# Power_Distribution_-_Rear_turn_and_brake.net
KiCad netlist of a schematic drawn in Altium Designer
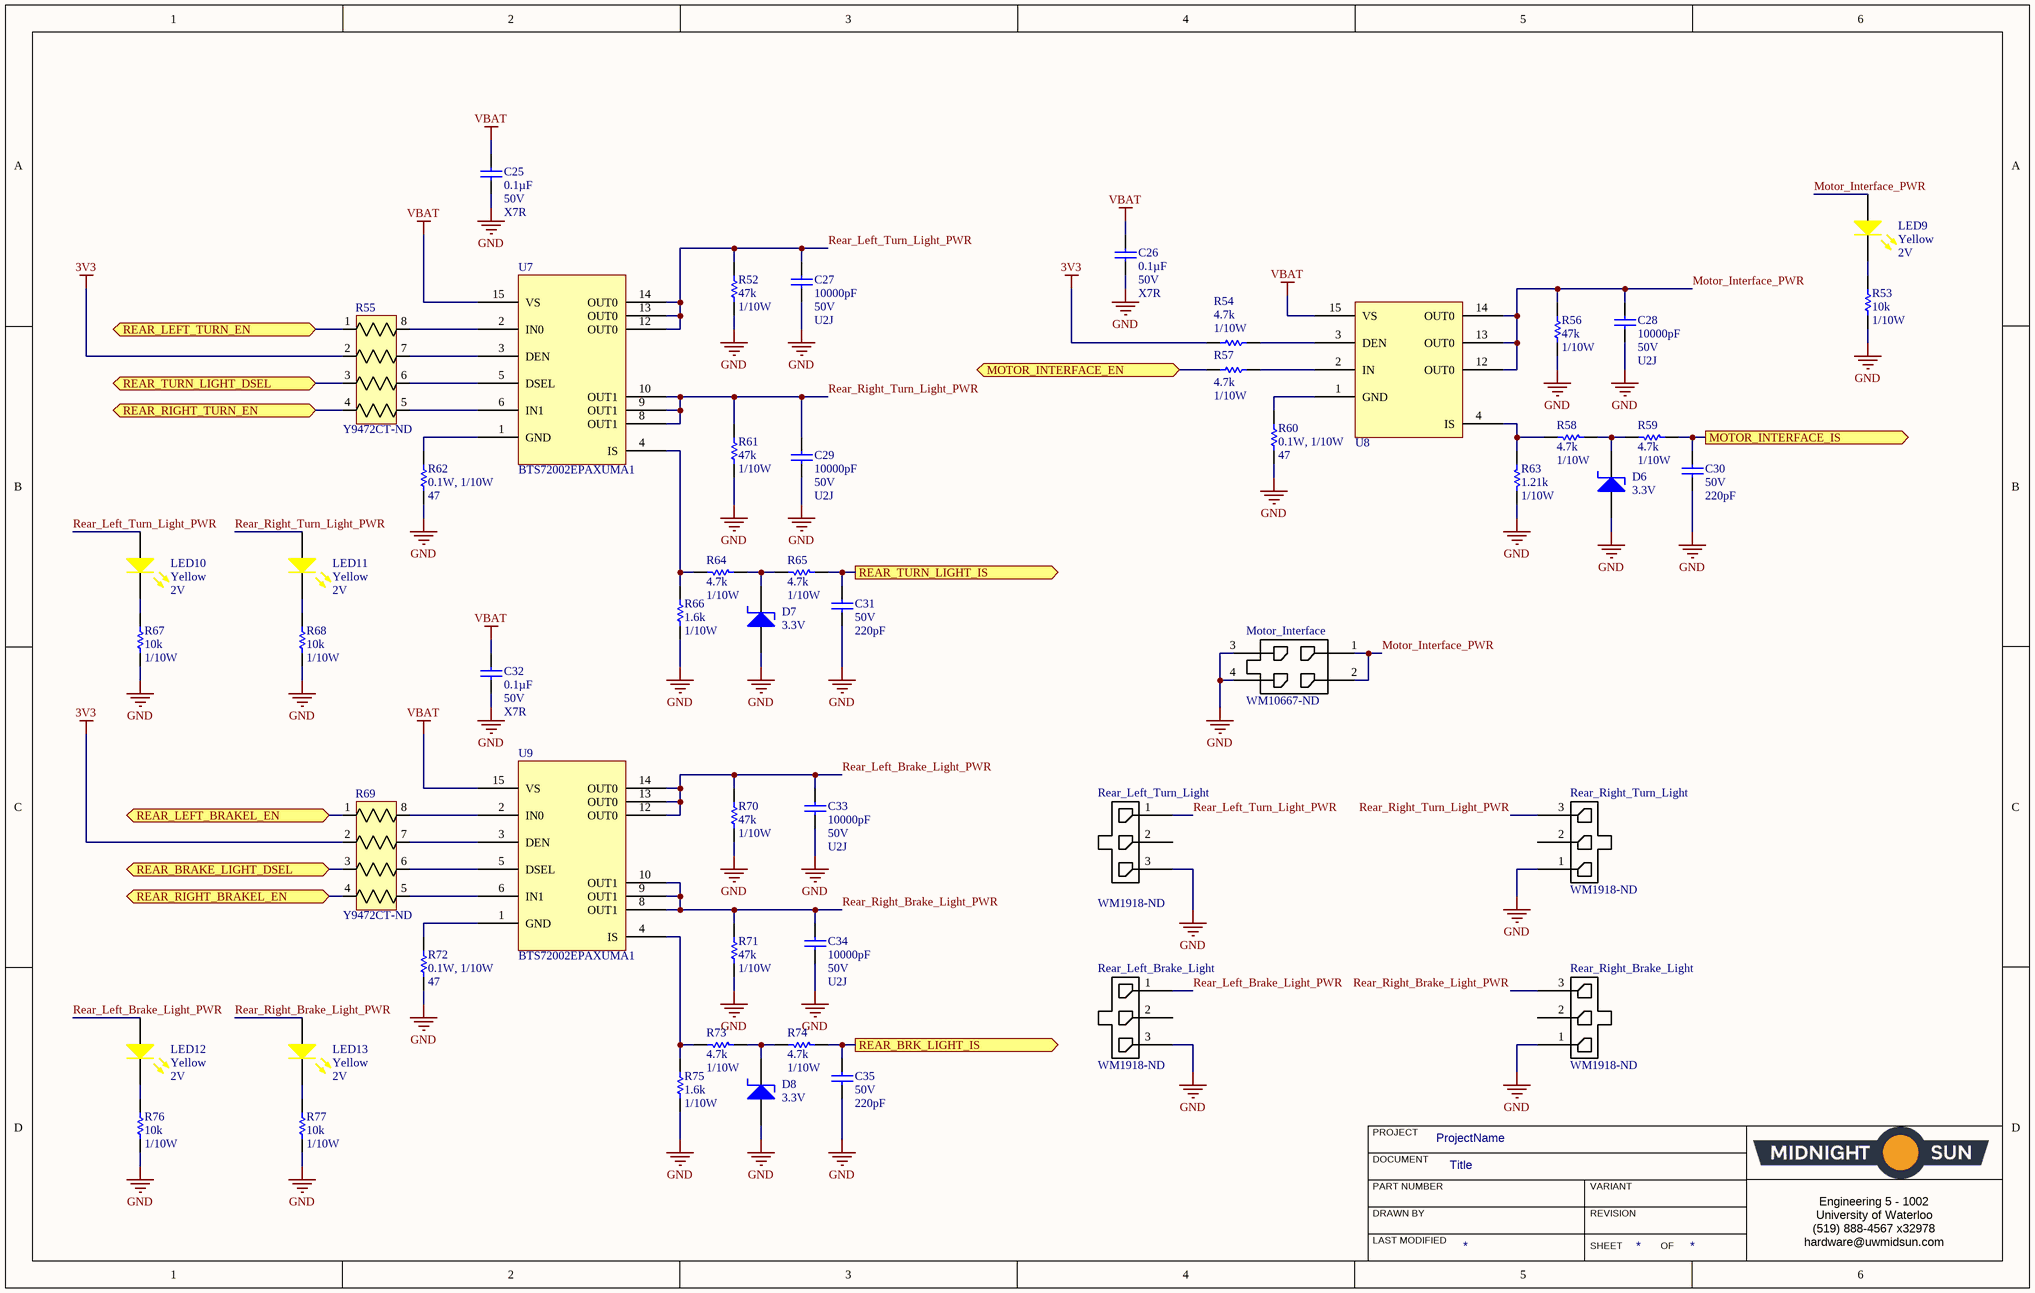
[diagram p0: Power Distribution - Rear turn and brake light, and Motor Interface.SchDoc]

(export (version "E")
  (design (tool "Eeschema 10.0.6"))
  (components
    (comp (ref "C25")
      (value "CAP CER 0.1UF 50V 10% X7R 0603")
      (footprint "CAP, 0603")
      (description "0.10µF ±10% 50V Ceramic Capacitor X7R 0603 (1608 Metric)")
      (fields
        (field (name "TOLERANCE") "±10%")
        (field (name "CAPACITANCE") "0.1µF")
        (field (name "VOLTAGE") "50V")
        (field (name "TEMPERATURE COEFFICIENT") "X7R")
      )
      (libsource (lib "Schematic Diagrams") (part "CAP CER 0.1UF 50V 10% X7R 0603"))
    )
    (comp (ref "C26")
      (value "CAP CER 0.1UF 50V 10% X7R 0603")
      (footprint "CAP, 0603")
      (description "0.10µF ±10% 50V Ceramic Capacitor X7R 0603 (1608 Metric)")
      (fields
        (field (name "TOLERANCE") "±10%")
        (field (name "CAPACITANCE") "0.1µF")
        (field (name "VOLTAGE") "50V")
        (field (name "TEMPERATURE COEFFICIENT") "X7R")
      )
      (libsource (lib "Schematic Diagrams") (part "CAP CER 0.1UF 50V 10% X7R 0603"))
    )
    (comp (ref "C27")
      (value "CAP CER 10nF 50V 5% X7R 0603")
      (footprint "CAP, 0603")
      (description "10000pF ±5% 50V Ceramic Capacitor U2J 0603 (1608 Metric)")
      (fields
        (field (name "TOLERANCE") "±5%")
        (field (name "CAPACITANCE") "10000pF")
        (field (name "VOLTAGE") "50V")
        (field (name "TEMPERATURE COEFFICIENT") "U2J")
      )
      (libsource (lib "Schematic Diagrams") (part "CAP CER 10nF 50V 5% X7R 0603"))
    )
    (comp (ref "C28")
      (value "CAP CER 10nF 50V 5% X7R 0603")
      (footprint "CAP, 0603")
      (description "10000pF ±5% 50V Ceramic Capacitor U2J 0603 (1608 Metric)")
      (fields
        (field (name "TOLERANCE") "±5%")
        (field (name "CAPACITANCE") "10000pF")
        (field (name "VOLTAGE") "50V")
        (field (name "TEMPERATURE COEFFICIENT") "U2J")
      )
      (libsource (lib "Schematic Diagrams") (part "CAP CER 10nF 50V 5% X7R 0603"))
    )
    (comp (ref "C29")
      (value "CAP CER 10nF 50V 5% X7R 0603")
      (footprint "CAP, 0603")
      (description "10000pF ±5% 50V Ceramic Capacitor U2J 0603 (1608 Metric)")
      (fields
        (field (name "TOLERANCE") "±5%")
        (field (name "CAPACITANCE") "10000pF")
        (field (name "VOLTAGE") "50V")
        (field (name "TEMPERATURE COEFFICIENT") "U2J")
      )
      (libsource (lib "Schematic Diagrams") (part "CAP CER 10nF 50V 5% X7R 0603"))
    )
    (comp (ref "C30")
      (value "CAP CER 220PF 50V C0G/NP0 0603")
      (footprint "CAP, 0603")
      (description "220pF ±5% 50V Ceramic Capacitor C0G, NP0 0603 (1608 Metric)")
      (fields
        (field (name "MANUFACTURER") "KEMET")
        (field (name "TOLERANCE") "5%")
        (field (name "VOLTAGE RATING") "50V")
        (field (name "CAPACITANCE") "220pF")
      )
      (libsource (lib "Schematic Diagrams") (part "CAP CER 220PF 50V C0G/NP0 0603"))
    )
    (comp (ref "C31")
      (value "CAP CER 220PF 50V C0G/NP0 0603")
      (footprint "CAP, 0603")
      (description "220pF ±5% 50V Ceramic Capacitor C0G, NP0 0603 (1608 Metric)")
      (fields
        (field (name "MANUFACTURER") "KEMET")
        (field (name "TOLERANCE") "5%")
        (field (name "VOLTAGE RATING") "50V")
        (field (name "CAPACITANCE") "220pF")
      )
      (libsource (lib "Schematic Diagrams") (part "CAP CER 220PF 50V C0G/NP0 0603"))
    )
    (comp (ref "C32")
      (value "CAP CER 0.1UF 50V 10% X7R 0603")
      (footprint "CAP, 0603")
      (description "0.10µF ±10% 50V Ceramic Capacitor X7R 0603 (1608 Metric)")
      (fields
        (field (name "TOLERANCE") "±10%")
        (field (name "CAPACITANCE") "0.1µF")
        (field (name "VOLTAGE") "50V")
        (field (name "TEMPERATURE COEFFICIENT") "X7R")
      )
      (libsource (lib "Schematic Diagrams") (part "CAP CER 0.1UF 50V 10% X7R 0603"))
    )
    (comp (ref "C33")
      (value "CAP CER 10nF 50V 5% X7R 0603")
      (footprint "CAP, 0603")
      (description "10000pF ±5% 50V Ceramic Capacitor U2J 0603 (1608 Metric)")
      (fields
        (field (name "TOLERANCE") "±5%")
        (field (name "CAPACITANCE") "10000pF")
        (field (name "VOLTAGE") "50V")
        (field (name "TEMPERATURE COEFFICIENT") "U2J")
      )
      (libsource (lib "Schematic Diagrams") (part "CAP CER 10nF 50V 5% X7R 0603"))
    )
    (comp (ref "C34")
      (value "CAP CER 10nF 50V 5% X7R 0603")
      (footprint "CAP, 0603")
      (description "10000pF ±5% 50V Ceramic Capacitor U2J 0603 (1608 Metric)")
      (fields
        (field (name "TOLERANCE") "±5%")
        (field (name "CAPACITANCE") "10000pF")
        (field (name "VOLTAGE") "50V")
        (field (name "TEMPERATURE COEFFICIENT") "U2J")
      )
      (libsource (lib "Schematic Diagrams") (part "CAP CER 10nF 50V 5% X7R 0603"))
    )
    (comp (ref "C35")
      (value "CAP CER 220PF 50V C0G/NP0 0603")
      (footprint "CAP, 0603")
      (description "220pF ±5% 50V Ceramic Capacitor C0G, NP0 0603 (1608 Metric)")
      (fields
        (field (name "MANUFACTURER") "KEMET")
        (field (name "TOLERANCE") "5%")
        (field (name "VOLTAGE RATING") "50V")
        (field (name "CAPACITANCE") "220pF")
      )
      (libsource (lib "Schematic Diagrams") (part "CAP CER 220PF 50V C0G/NP0 0603"))
    )
    (comp (ref "D6")
      (value "DIODE ZENER 3.3V 200MW SOD323")
      (footprint "sod-323")
      (description "Zener Diode 3.3V 200mW ±5% Surface Mount SOD-323")
      (fields (field (name "VOLTAGE") "3.3V"))
      (libsource (lib "Schematic Diagrams") (part "DIODE ZENER 3.3V 200MW SOD323"))
    )
    (comp (ref "D7")
      (value "DIODE ZENER 3.3V 200MW SOD323")
      (footprint "sod-323")
      (description "Zener Diode 3.3V 200mW ±5% Surface Mount SOD-323")
      (fields (field (name "VOLTAGE") "3.3V"))
      (libsource (lib "Schematic Diagrams") (part "DIODE ZENER 3.3V 200MW SOD323"))
    )
    (comp (ref "D8")
      (value "DIODE ZENER 3.3V 200MW SOD323")
      (footprint "sod-323")
      (description "Zener Diode 3.3V 200mW ±5% Surface Mount SOD-323")
      (fields (field (name "VOLTAGE") "3.3V"))
      (libsource (lib "Schematic Diagrams") (part "DIODE ZENER 3.3V 200MW SOD323"))
    )
    (comp (ref "LED9")
      (value "LED YELLOW CLEAR 2.1V 0603")
      (footprint "LED_0603")
      (description "Yellow 590nm LED Indication - Discrete 2V 0603 (1608 Metric)")
      (fields
        (field (name "MANUFACTURER") "Wurth Electronics Inc.")
        (field (name "MANUFACTURER PART NUMBER") "150060YS75000")
        (field (name "COLOR") "Yellow")
        (field (name "VOLTAGE - FORWARD (VF) (TYP)") "2V")
      )
      (libsource (lib "Schematic Diagrams") (part "LED YELLOW CLEAR 2.1V 0603"))
    )
    (comp (ref "LED10")
      (value "LED YELLOW CLEAR 2.1V 0603")
      (footprint "LED_0603")
      (description "Yellow 590nm LED Indication - Discrete 2V 0603 (1608 Metric)")
      (fields
        (field (name "MANUFACTURER") "Wurth Electronics Inc.")
        (field (name "MANUFACTURER PART NUMBER") "150060YS75000")
        (field (name "COLOR") "Yellow")
        (field (name "VOLTAGE - FORWARD (VF) (TYP)") "2V")
      )
      (libsource (lib "Schematic Diagrams") (part "LED YELLOW CLEAR 2.1V 0603"))
    )
    (comp (ref "LED11")
      (value "LED YELLOW CLEAR 2.1V 0603")
      (footprint "LED_0603")
      (description "Yellow 590nm LED Indication - Discrete 2V 0603 (1608 Metric)")
      (fields
        (field (name "MANUFACTURER") "Wurth Electronics Inc.")
        (field (name "MANUFACTURER PART NUMBER") "150060YS75000")
        (field (name "COLOR") "Yellow")
        (field (name "VOLTAGE - FORWARD (VF) (TYP)") "2V")
      )
      (libsource (lib "Schematic Diagrams") (part "LED YELLOW CLEAR 2.1V 0603"))
    )
    (comp (ref "LED12")
      (value "LED YELLOW CLEAR 2.1V 0603")
      (footprint "LED_0603")
      (description "Yellow 590nm LED Indication - Discrete 2V 0603 (1608 Metric)")
      (fields
        (field (name "MANUFACTURER") "Wurth Electronics Inc.")
        (field (name "MANUFACTURER PART NUMBER") "150060YS75000")
        (field (name "COLOR") "Yellow")
        (field (name "VOLTAGE - FORWARD (VF) (TYP)") "2V")
      )
      (libsource (lib "Schematic Diagrams") (part "LED YELLOW CLEAR 2.1V 0603"))
    )
    (comp (ref "LED13")
      (value "LED YELLOW CLEAR 2.1V 0603")
      (footprint "LED_0603")
      (description "Yellow 590nm LED Indication - Discrete 2V 0603 (1608 Metric)")
      (fields
        (field (name "MANUFACTURER") "Wurth Electronics Inc.")
        (field (name "MANUFACTURER PART NUMBER") "150060YS75000")
        (field (name "COLOR") "Yellow")
        (field (name "VOLTAGE - FORWARD (VF) (TYP)") "2V")
      )
      (libsource (lib "Schematic Diagrams") (part "LED YELLOW CLEAR 2.1V 0603"))
    )
    (comp (ref "Motor_Interface")
      (value "CONN 4POS MICRO-FIT 3mm")
      (footprint "CONN 4POS MICROFIT (2x2)")
      (fields
        (field (name "MANUFACTURER") "Molex, LLC")
        (field (name "MANUFACTURER PART NUMBER") "430450427")
        (field (name "SUPPLIER PART NUMBER 1") "WM10667-ND")
      )
      (libsource (lib "Schematic Diagrams") (part "CONN 4POS MICRO-FIT 3mm"))
    )
    (comp (ref "R52")
      (value "RES 47K OHM 1% 1/10W 0603")
      (footprint "RES, 0603")
      (description "47 kOhms ±1% 0.1W, 1/10W Chip Resistor 0603 (1608 Metric) Automotive AEC-Q200 Thick Film")
      (fields
        (field (name "MANUFACTURER") "Panasonic")
        (field (name "MANUFACTURER PART NUMBER") "ERJ3EKF4702V")
        (field (name "RESISTANCE") "47k")
        (field (name "POWER RATING") "1/10W")
      )
      (libsource (lib "Schematic Diagrams") (part "RES 47K OHM 1% 1/10W 0603"))
    )
    (comp (ref "R53")
      (value "RES 10K OHM 1% 1/10W 0603")
      (footprint "RES, 0603")
      (description "RES SMD 10K OHM 1% 1/10W 0603")
      (fields
        (field (name "TOLERANCE") "±1%")
        (field (name "RESISTANCE") "10k")
        (field (name "POWER") "1/10W")
      )
      (libsource (lib "Schematic Diagrams") (part "RES 10K OHM 1% 1/10W 0603"))
    )
    (comp (ref "R54")
      (value "RES 4.7K OHM 1% 1/10W 0603")
      (footprint "RES, 0603")
      (description "4.7k Ohm ±1% 0.1W, 1/10W Chip Resistor 0603 (1608 Metric) Moisture Resistant Thick Film")
      (fields
        (field (name "TOLERANCE") "±1%")
        (field (name "RESISTANCE (OHMS)") "4.7k")
        (field (name "POWER (WATTS)") "1/10W")
      )
      (libsource (lib "Schematic Diagrams") (part "RES 4.7K OHM 1% 1/10W 0603"))
    )
    (comp (ref "R55")
      (value "RES ARRAY 4 RES 4.7K OHM 1206")
      (footprint "RES ARRAY 4RES 1206")
      (fields (field (name "TOLERANCE") "±5%") (field (name "SUPPLIER PART NUMBER 1") "Y9472CT-ND"))
      (libsource (lib "Schematic Diagrams") (part "RES ARRAY 4 RES 4.7K OHM 1206"))
    )
    (comp (ref "R56")
      (value "RES 47K OHM 1% 1/10W 0603")
      (footprint "RES, 0603")
      (description "47 kOhms ±1% 0.1W, 1/10W Chip Resistor 0603 (1608 Metric) Automotive AEC-Q200 Thick Film")
      (fields
        (field (name "MANUFACTURER") "Panasonic")
        (field (name "MANUFACTURER PART NUMBER") "ERJ3EKF4702V")
        (field (name "RESISTANCE") "47k")
        (field (name "POWER RATING") "1/10W")
      )
      (libsource (lib "Schematic Diagrams") (part "RES 47K OHM 1% 1/10W 0603"))
    )
    (comp (ref "R57")
      (value "RES 4.7K OHM 1% 1/10W 0603")
      (footprint "RES, 0603")
      (description "4.7k Ohm ±1% 0.1W, 1/10W Chip Resistor 0603 (1608 Metric) Moisture Resistant Thick Film")
      (fields
        (field (name "TOLERANCE") "±1%")
        (field (name "RESISTANCE (OHMS)") "4.7k")
        (field (name "POWER (WATTS)") "1/10W")
      )
      (libsource (lib "Schematic Diagrams") (part "RES 4.7K OHM 1% 1/10W 0603"))
    )
    (comp (ref "R58")
      (value "RES 4.7K OHM 1% 1/10W 0603")
      (footprint "RES, 0603")
      (description "4.7k Ohm ±1% 0.1W, 1/10W Chip Resistor 0603 (1608 Metric) Moisture Resistant Thick Film")
      (fields
        (field (name "TOLERANCE") "±1%")
        (field (name "RESISTANCE (OHMS)") "4.7k")
        (field (name "POWER (WATTS)") "1/10W")
      )
      (libsource (lib "Schematic Diagrams") (part "RES 4.7K OHM 1% 1/10W 0603"))
    )
    (comp (ref "R59")
      (value "RES 4.7K OHM 1% 1/10W 0603")
      (footprint "RES, 0603")
      (description "4.7k Ohm ±1% 0.1W, 1/10W Chip Resistor 0603 (1608 Metric) Moisture Resistant Thick Film")
      (fields
        (field (name "TOLERANCE") "±1%")
        (field (name "RESISTANCE (OHMS)") "4.7k")
        (field (name "POWER (WATTS)") "1/10W")
      )
      (libsource (lib "Schematic Diagrams") (part "RES 4.7K OHM 1% 1/10W 0603"))
    )
    (comp (ref "R60")
      (value "RES SMD 47 OHM 1% 1/10W 0603")
      (footprint "RES, 0603")
      (fields
        (field (name "TOLERANCE") "±1%")
        (field (name "POWER (WATTS)") "0.1W, 1/10W")
        (field (name "VALUES") "47")
      )
      (libsource (lib "Schematic Diagrams") (part "RES SMD 47 OHM 1% 1/10W 0603"))
    )
    (comp (ref "R61")
      (value "RES 47K OHM 1% 1/10W 0603")
      (footprint "RES, 0603")
      (description "47 kOhms ±1% 0.1W, 1/10W Chip Resistor 0603 (1608 Metric) Automotive AEC-Q200 Thick Film")
      (fields
        (field (name "MANUFACTURER") "Panasonic")
        (field (name "MANUFACTURER PART NUMBER") "ERJ3EKF4702V")
        (field (name "RESISTANCE") "47k")
        (field (name "POWER RATING") "1/10W")
      )
      (libsource (lib "Schematic Diagrams") (part "RES 47K OHM 1% 1/10W 0603"))
    )
    (comp (ref "R62")
      (value "RES SMD 47 OHM 1% 1/10W 0603")
      (footprint "RES, 0603")
      (fields
        (field (name "TOLERANCE") "±1%")
        (field (name "POWER (WATTS)") "0.1W, 1/10W")
        (field (name "VALUES") "47")
      )
      (libsource (lib "Schematic Diagrams") (part "RES SMD 47 OHM 1% 1/10W 0603"))
    )
    (comp (ref "R63")
      (value "RES 1.21K OHM 1% 1/10W 0603")
      (footprint "RES, 0603")
      (description "1.21k Ohm ±1% 0.1W, 1/10W Chip Resistor 0603 (1608 Metric) Moisture Resistant Thick Film")
      (fields
        (field (name "TOLERANCE") "±1%")
        (field (name "RESISTANCE") "1.21k")
        (field (name "POWER") "1/10W")
      )
      (libsource (lib "Schematic Diagrams") (part "RES 1.21K OHM 1% 1/10W 0603"))
    )
    (comp (ref "R64")
      (value "RES 4.7K OHM 1% 1/10W 0603")
      (footprint "RES, 0603")
      (description "4.7k Ohm ±1% 0.1W, 1/10W Chip Resistor 0603 (1608 Metric) Moisture Resistant Thick Film")
      (fields
        (field (name "TOLERANCE") "±1%")
        (field (name "RESISTANCE (OHMS)") "4.7k")
        (field (name "POWER (WATTS)") "1/10W")
      )
      (libsource (lib "Schematic Diagrams") (part "RES 4.7K OHM 1% 1/10W 0603"))
    )
    (comp (ref "R65")
      (value "RES 4.7K OHM 1% 1/10W 0603")
      (footprint "RES, 0603")
      (description "4.7k Ohm ±1% 0.1W, 1/10W Chip Resistor 0603 (1608 Metric) Moisture Resistant Thick Film")
      (fields
        (field (name "TOLERANCE") "±1%")
        (field (name "RESISTANCE (OHMS)") "4.7k")
        (field (name "POWER (WATTS)") "1/10W")
      )
      (libsource (lib "Schematic Diagrams") (part "RES 4.7K OHM 1% 1/10W 0603"))
    )
    (comp (ref "R66")
      (value "RES 1.6K OHM 1% 1/10W 0603")
      (footprint "RES, 0603")
      (description "1.6 kOhms ±1% 0.1W, 1/10W Chip Resistor 0603 (1608 Metric) Moisture Resistant Thick Film")
      (fields
        (field (name "MANUFACTURER") "Yageo")
        (field (name "MANUFACTURER PART NUMBER") "RC0603FR-071K6L")
        (field (name "RESISTANCE") "1.6k")
        (field (name "POWER RATING") "1/10W")
      )
      (libsource (lib "Schematic Diagrams") (part "RES 1.6K OHM 1% 1/10W 0603"))
    )
    (comp (ref "R67")
      (value "RES 10K OHM 1% 1/10W 0603")
      (footprint "RES, 0603")
      (description "RES SMD 10K OHM 1% 1/10W 0603")
      (fields
        (field (name "TOLERANCE") "±1%")
        (field (name "RESISTANCE") "10k")
        (field (name "POWER") "1/10W")
      )
      (libsource (lib "Schematic Diagrams") (part "RES 10K OHM 1% 1/10W 0603"))
    )
    (comp (ref "R68")
      (value "RES 10K OHM 1% 1/10W 0603")
      (footprint "RES, 0603")
      (description "RES SMD 10K OHM 1% 1/10W 0603")
      (fields
        (field (name "TOLERANCE") "±1%")
        (field (name "RESISTANCE") "10k")
        (field (name "POWER") "1/10W")
      )
      (libsource (lib "Schematic Diagrams") (part "RES 10K OHM 1% 1/10W 0603"))
    )
    (comp (ref "R69")
      (value "RES ARRAY 4 RES 4.7K OHM 1206")
      (footprint "RES ARRAY 4RES 1206")
      (fields (field (name "TOLERANCE") "±5%") (field (name "SUPPLIER PART NUMBER 1") "Y9472CT-ND"))
      (libsource (lib "Schematic Diagrams") (part "RES ARRAY 4 RES 4.7K OHM 1206"))
    )
    (comp (ref "R70")
      (value "RES 47K OHM 1% 1/10W 0603")
      (footprint "RES, 0603")
      (description "47 kOhms ±1% 0.1W, 1/10W Chip Resistor 0603 (1608 Metric) Automotive AEC-Q200 Thick Film")
      (fields
        (field (name "MANUFACTURER") "Panasonic")
        (field (name "MANUFACTURER PART NUMBER") "ERJ3EKF4702V")
        (field (name "RESISTANCE") "47k")
        (field (name "POWER RATING") "1/10W")
      )
      (libsource (lib "Schematic Diagrams") (part "RES 47K OHM 1% 1/10W 0603"))
    )
    (comp (ref "R71")
      (value "RES 47K OHM 1% 1/10W 0603")
      (footprint "RES, 0603")
      (description "47 kOhms ±1% 0.1W, 1/10W Chip Resistor 0603 (1608 Metric) Automotive AEC-Q200 Thick Film")
      (fields
        (field (name "MANUFACTURER") "Panasonic")
        (field (name "MANUFACTURER PART NUMBER") "ERJ3EKF4702V")
        (field (name "RESISTANCE") "47k")
        (field (name "POWER RATING") "1/10W")
      )
      (libsource (lib "Schematic Diagrams") (part "RES 47K OHM 1% 1/10W 0603"))
    )
    (comp (ref "R72")
      (value "RES SMD 47 OHM 1% 1/10W 0603")
      (footprint "RES, 0603")
      (fields
        (field (name "TOLERANCE") "±1%")
        (field (name "POWER (WATTS)") "0.1W, 1/10W")
        (field (name "VALUES") "47")
      )
      (libsource (lib "Schematic Diagrams") (part "RES SMD 47 OHM 1% 1/10W 0603"))
    )
    (comp (ref "R73")
      (value "RES 4.7K OHM 1% 1/10W 0603")
      (footprint "RES, 0603")
      (description "4.7k Ohm ±1% 0.1W, 1/10W Chip Resistor 0603 (1608 Metric) Moisture Resistant Thick Film")
      (fields
        (field (name "TOLERANCE") "±1%")
        (field (name "RESISTANCE (OHMS)") "4.7k")
        (field (name "POWER (WATTS)") "1/10W")
      )
      (libsource (lib "Schematic Diagrams") (part "RES 4.7K OHM 1% 1/10W 0603"))
    )
    (comp (ref "R74")
      (value "RES 4.7K OHM 1% 1/10W 0603")
      (footprint "RES, 0603")
      (description "4.7k Ohm ±1% 0.1W, 1/10W Chip Resistor 0603 (1608 Metric) Moisture Resistant Thick Film")
      (fields
        (field (name "TOLERANCE") "±1%")
        (field (name "RESISTANCE (OHMS)") "4.7k")
        (field (name "POWER (WATTS)") "1/10W")
      )
      (libsource (lib "Schematic Diagrams") (part "RES 4.7K OHM 1% 1/10W 0603"))
    )
    (comp (ref "R75")
      (value "RES 1.6K OHM 1% 1/10W 0603")
      (footprint "RES, 0603")
      (description "1.6 kOhms ±1% 0.1W, 1/10W Chip Resistor 0603 (1608 Metric) Moisture Resistant Thick Film")
      (fields
        (field (name "MANUFACTURER") "Yageo")
        (field (name "MANUFACTURER PART NUMBER") "RC0603FR-071K6L")
        (field (name "RESISTANCE") "1.6k")
        (field (name "POWER RATING") "1/10W")
      )
      (libsource (lib "Schematic Diagrams") (part "RES 1.6K OHM 1% 1/10W 0603"))
    )
    (comp (ref "R76")
      (value "RES 10K OHM 1% 1/10W 0603")
      (footprint "RES, 0603")
      (description "RES SMD 10K OHM 1% 1/10W 0603")
      (fields
        (field (name "TOLERANCE") "±1%")
        (field (name "RESISTANCE") "10k")
        (field (name "POWER") "1/10W")
      )
      (libsource (lib "Schematic Diagrams") (part "RES 10K OHM 1% 1/10W 0603"))
    )
    (comp (ref "R77")
      (value "RES 10K OHM 1% 1/10W 0603")
      (footprint "RES, 0603")
      (description "RES SMD 10K OHM 1% 1/10W 0603")
      (fields
        (field (name "TOLERANCE") "±1%")
        (field (name "RESISTANCE") "10k")
        (field (name "POWER") "1/10W")
      )
      (libsource (lib "Schematic Diagrams") (part "RES 10K OHM 1% 1/10W 0603"))
    )
    (comp (ref "Rear_Left_Brake_Light")
      (value "CONN 3POS MICROFIT")
      (footprint "CONN, 3 POS MICROFIT")
      (description "Connector Header Through Hole 3 position 0.118\" (3.00mm)")
      (fields (field (name "SUPPLIER PART NUMBER 1") "WM1918-ND"))
      (libsource (lib "Schematic Diagrams") (part "CONN 3POS MICROFIT"))
    )
    (comp (ref "Rear_Left_Turn_Light")
      (value "CONN 3POS MICROFIT")
      (footprint "CONN, 3 POS MICROFIT")
      (description "Connector Header Through Hole 3 position 0.118\" (3.00mm)")
      (fields (field (name "SUPPLIER PART NUMBER 1") "WM1918-ND"))
      (libsource (lib "Schematic Diagrams") (part "CONN 3POS MICROFIT"))
    )
    (comp (ref "Rear_Right_Brake_Light")
      (value "CONN 3POS MICROFIT")
      (footprint "CONN, 3 POS MICROFIT")
      (description "Connector Header Through Hole 3 position 0.118\" (3.00mm)")
      (fields (field (name "SUPPLIER PART NUMBER 1") "WM1918-ND"))
      (libsource (lib "Schematic Diagrams") (part "CONN 3POS MICROFIT"))
    )
    (comp (ref "Rear_Right_Turn_Light")
      (value "CONN 3POS MICROFIT")
      (footprint "CONN, 3 POS MICROFIT")
      (description "Connector Header Through Hole 3 position 0.118\" (3.00mm)")
      (fields (field (name "SUPPLIER PART NUMBER 1") "WM1918-ND"))
      (libsource (lib "Schematic Diagrams") (part "CONN 3POS MICROFIT"))
    )
    (comp (ref "U7")
      (value "IC LOAD SWITCH BTS7200-2EPA PG-TSDSO-14_1")
      (footprint "IC LOAD SWITCH PG-TSDSO-14-22")
      (description "Power Switch/Driver 1:1 N-Channel 1.2A PG-TSDSO-14-22")
      (fields
        (field (name "MANUFACTURER") "Infineon")
        (field (name "MANUFACTURER PART NUMBER") "BTS72002EPAXUMA1")
      )
      (libsource (lib "Schematic Diagrams") (part "IC LOAD SWITCH BTS7200-2EPA PG-TSDSO-14_1"))
    )
    (comp (ref "U8")
      (value "IC LOAD SWITCH BTS70401EPA PG-TSDSO-14-22")
      (footprint "IC LOAD SWITCH PG-TSDSO-14-22")
      (description "Power Switch/Driver 1:1 N-Channel 4.5A PG-TSDSO-14-22")
      (fields
        (field (name "MANUFACTURER") "Infineon")
        (field (name "MANUFACTURER PART NUMBER") "BTS70401EPAXUMA1")
      )
      (libsource (lib "Schematic Diagrams") (part "IC LOAD SWITCH BTS70401EPA PG-TSDSO-14-22"))
    )
    (comp (ref "U9")
      (value "IC LOAD SWITCH BTS7200-2EPA PG-TSDSO-14_1")
      (footprint "IC LOAD SWITCH PG-TSDSO-14-22")
      (description "Power Switch/Driver 1:1 N-Channel 1.2A PG-TSDSO-14-22")
      (fields
        (field (name "MANUFACTURER") "Infineon")
        (field (name "MANUFACTURER PART NUMBER") "BTS72002EPAXUMA1")
      )
      (libsource (lib "Schematic Diagrams") (part "IC LOAD SWITCH BTS7200-2EPA PG-TSDSO-14_1"))
    )
  )
  (nets
    (net (code "1") (name "/MOTOR_INTERFACE_EN") (class "Default")
      (node (ref "R57") (pin "1") (pinfunction "1_1") (pintype "passive"))
    )
    (net (code "2") (name "/MOTOR_INTERFACE_IS") (class "Default")
      (node (ref "C30") (pin "1") (pinfunction "1_1") (pintype "passive"))
      (node (ref "R59") (pin "1") (pinfunction "1_1") (pintype "passive"))
    )
    (net (code "3") (name "/Motor_Interface_PWR") (class "Default")
      (node (ref "C28") (pin "1") (pinfunction "1_1") (pintype "passive"))
      (node (ref "LED9") (pin "1") (pinfunction "A_1") (pintype "passive"))
      (node (ref "Motor_Interface") (pin "1") (pinfunction "1_1") (pintype "passive"))
      (node (ref "Motor_Interface") (pin "2") (pinfunction "2_2") (pintype "passive"))
      (node (ref "R56") (pin "1") (pinfunction "1_1") (pintype "passive"))
      (node (ref "U8") (pin "12") (pinfunction "OUT0_12") (pintype "passive"))
      (node (ref "U8") (pin "13") (pinfunction "OUT0_13") (pintype "passive"))
      (node (ref "U8") (pin "14") (pinfunction "OUT0_14") (pintype "passive"))
    )
    (net (code "4") (name "/REAR_BRAKE_LIGHT_DSEL") (class "Default")
      (node (ref "R69") (pin "3") (pinfunction "3_3") (pintype "passive"))
    )
    (net (code "5") (name "/REAR_BRK_LIGHT_IS") (class "Default")
      (node (ref "C35") (pin "1") (pinfunction "1_1") (pintype "passive"))
      (node (ref "R74") (pin "1") (pinfunction "1_1") (pintype "passive"))
    )
    (net (code "6") (name "/REAR_LEFT_BRAKEL_EN") (class "Default")
      (node (ref "R69") (pin "1") (pinfunction "1_1") (pintype "passive"))
    )
    (net (code "7") (name "/REAR_LEFT_TURN_EN") (class "Default")
      (node (ref "R55") (pin "1") (pinfunction "1_1") (pintype "passive"))
    )
    (net (code "8") (name "/REAR_RIGHT_BRAKEL_EN") (class "Default")
      (node (ref "R69") (pin "4") (pinfunction "4_4") (pintype "passive"))
    )
    (net (code "9") (name "/REAR_RIGHT_TURN_EN") (class "Default")
      (node (ref "R55") (pin "4") (pinfunction "4_4") (pintype "passive"))
    )
    (net (code "10") (name "/REAR_TURN_LIGHT_DSEL") (class "Default")
      (node (ref "R55") (pin "3") (pinfunction "3_3") (pintype "passive"))
    )
    (net (code "11") (name "/REAR_TURN_LIGHT_IS") (class "Default")
      (node (ref "C31") (pin "1") (pinfunction "1_1") (pintype "passive"))
      (node (ref "R65") (pin "1") (pinfunction "1_1") (pintype "passive"))
    )
    (net (code "12") (name "/Rear_Left_Brake_Light_PWR") (class "Default")
      (node (ref "C33") (pin "1") (pinfunction "1_1") (pintype "passive"))
      (node (ref "LED12") (pin "1") (pinfunction "A_1") (pintype "passive"))
      (node (ref "R70") (pin "1") (pinfunction "1_1") (pintype "passive"))
      (node (ref "Rear_Left_Brake_Light") (pin "1") (pinfunction "1_1") (pintype "passive"))
      (node (ref "U9") (pin "12") (pinfunction "OUT0_12") (pintype "passive"))
      (node (ref "U9") (pin "13") (pinfunction "OUT0_13") (pintype "passive"))
      (node (ref "U9") (pin "14") (pinfunction "OUT0_14") (pintype "passive"))
    )
    (net (code "13") (name "/Rear_Left_Turn_Light_PWR") (class "Default")
      (node (ref "C27") (pin "1") (pinfunction "1_1") (pintype "passive"))
      (node (ref "LED10") (pin "1") (pinfunction "A_1") (pintype "passive"))
      (node (ref "R52") (pin "1") (pinfunction "1_1") (pintype "passive"))
      (node (ref "Rear_Left_Turn_Light") (pin "1") (pinfunction "1_1") (pintype "passive"))
      (node (ref "U7") (pin "12") (pinfunction "OUT0_12") (pintype "passive"))
      (node (ref "U7") (pin "13") (pinfunction "OUT0_13") (pintype "passive"))
      (node (ref "U7") (pin "14") (pinfunction "OUT0_14") (pintype "passive"))
    )
    (net (code "14") (name "/Rear_Right_Brake_Light_PWR") (class "Default")
      (node (ref "C34") (pin "1") (pinfunction "1_1") (pintype "passive"))
      (node (ref "LED13") (pin "1") (pinfunction "A_1") (pintype "passive"))
      (node (ref "R71") (pin "1") (pinfunction "1_1") (pintype "passive"))
      (node (ref "Rear_Right_Brake_Light") (pin "3") (pinfunction "3_3") (pintype "passive"))
      (node (ref "U9") (pin "10") (pinfunction "OUT1_10") (pintype "passive"))
      (node (ref "U9") (pin "8") (pinfunction "OUT1_8") (pintype "passive"))
      (node (ref "U9") (pin "9") (pinfunction "OUT1_9") (pintype "passive"))
    )
    (net (code "15") (name "/Rear_Right_Turn_Light_PWR") (class "Default")
      (node (ref "C29") (pin "1") (pinfunction "1_1") (pintype "passive"))
      (node (ref "LED11") (pin "1") (pinfunction "A_1") (pintype "passive"))
      (node (ref "R61") (pin "1") (pinfunction "1_1") (pintype "passive"))
      (node (ref "Rear_Right_Turn_Light") (pin "3") (pinfunction "3_3") (pintype "passive"))
      (node (ref "U7") (pin "10") (pinfunction "OUT1_10") (pintype "passive"))
      (node (ref "U7") (pin "8") (pinfunction "OUT1_8") (pintype "passive"))
      (node (ref "U7") (pin "9") (pinfunction "OUT1_9") (pintype "passive"))
    )
    (net (code "16") (name "3V3") (class "Default")
      (node (ref "R54") (pin "1") (pinfunction "1_1") (pintype "passive"))
      (node (ref "R55") (pin "2") (pinfunction "2_2") (pintype "passive"))
      (node (ref "R69") (pin "2") (pinfunction "2_2") (pintype "passive"))
    )
    (net (code "17") (name "GND") (class "Default")
      (node (ref "C25") (pin "2") (pinfunction "2_2") (pintype "passive"))
      (node (ref "C26") (pin "2") (pinfunction "2_2") (pintype "passive"))
      (node (ref "C27") (pin "2") (pinfunction "2_2") (pintype "passive"))
      (node (ref "C28") (pin "2") (pinfunction "2_2") (pintype "passive"))
      (node (ref "C29") (pin "2") (pinfunction "2_2") (pintype "passive"))
      (node (ref "C30") (pin "2") (pinfunction "2_2") (pintype "passive"))
      (node (ref "C31") (pin "2") (pinfunction "2_2") (pintype "passive"))
      (node (ref "C32") (pin "2") (pinfunction "2_2") (pintype "passive"))
      (node (ref "C33") (pin "2") (pinfunction "2_2") (pintype "passive"))
      (node (ref "C34") (pin "2") (pinfunction "2_2") (pintype "passive"))
      (node (ref "C35") (pin "2") (pinfunction "2_2") (pintype "passive"))
      (node (ref "D6") (pin "1") (pinfunction "A_1") (pintype "passive"))
      (node (ref "D7") (pin "1") (pinfunction "A_1") (pintype "passive"))
      (node (ref "D8") (pin "1") (pinfunction "A_1") (pintype "passive"))
      (node (ref "Motor_Interface") (pin "3") (pinfunction "3_3") (pintype "passive"))
      (node (ref "Motor_Interface") (pin "4") (pinfunction "4_4") (pintype "passive"))
      (node (ref "R52") (pin "2") (pinfunction "2_2") (pintype "passive"))
      (node (ref "R53") (pin "2") (pinfunction "2_2") (pintype "passive"))
      (node (ref "R56") (pin "2") (pinfunction "2_2") (pintype "passive"))
      (node (ref "R60") (pin "2") (pinfunction "2_2") (pintype "passive"))
      (node (ref "R61") (pin "2") (pinfunction "2_2") (pintype "passive"))
      (node (ref "R62") (pin "2") (pinfunction "2_2") (pintype "passive"))
      (node (ref "R63") (pin "2") (pinfunction "2_2") (pintype "passive"))
      (node (ref "R66") (pin "2") (pinfunction "2_2") (pintype "passive"))
      (node (ref "R67") (pin "2") (pinfunction "2_2") (pintype "passive"))
      (node (ref "R68") (pin "2") (pinfunction "2_2") (pintype "passive"))
      (node (ref "R70") (pin "2") (pinfunction "2_2") (pintype "passive"))
      (node (ref "R71") (pin "2") (pinfunction "2_2") (pintype "passive"))
      (node (ref "R72") (pin "2") (pinfunction "2_2") (pintype "passive"))
      (node (ref "R75") (pin "2") (pinfunction "2_2") (pintype "passive"))
      (node (ref "R76") (pin "2") (pinfunction "2_2") (pintype "passive"))
      (node (ref "R77") (pin "2") (pinfunction "2_2") (pintype "passive"))
      (node (ref "Rear_Left_Brake_Light") (pin "3") (pinfunction "3_3") (pintype "passive"))
      (node (ref "Rear_Left_Turn_Light") (pin "3") (pinfunction "3_3") (pintype "passive"))
      (node (ref "Rear_Right_Brake_Light") (pin "1") (pinfunction "1_1") (pintype "passive"))
      (node (ref "Rear_Right_Turn_Light") (pin "1") (pinfunction "1_1") (pintype "passive"))
    )
    (net (code "18") (name "Net-(D6-K)") (class "Default")
      (node (ref "D6") (pin "2") (pinfunction "K_2") (pintype "passive"))
      (node (ref "R58") (pin "1") (pinfunction "1_1") (pintype "passive"))
      (node (ref "R59") (pin "2") (pinfunction "2_2") (pintype "passive"))
    )
    (net (code "19") (name "Net-(D7-K)") (class "Default")
      (node (ref "D7") (pin "2") (pinfunction "K_2") (pintype "passive"))
      (node (ref "R64") (pin "1") (pinfunction "1_1") (pintype "passive"))
      (node (ref "R65") (pin "2") (pinfunction "2_2") (pintype "passive"))
    )
    (net (code "20") (name "Net-(D8-K)") (class "Default")
      (node (ref "D8") (pin "2") (pinfunction "K_2") (pintype "passive"))
      (node (ref "R73") (pin "1") (pinfunction "1_1") (pintype "passive"))
      (node (ref "R74") (pin "2") (pinfunction "2_2") (pintype "passive"))
    )
    (net (code "21") (name "Net-(LED9-K)") (class "Default")
      (node (ref "LED9") (pin "2") (pinfunction "K_2") (pintype "passive"))
      (node (ref "R53") (pin "1") (pinfunction "1_1") (pintype "passive"))
    )
    (net (code "22") (name "Net-(LED10-K)") (class "Default")
      (node (ref "LED10") (pin "2") (pinfunction "K_2") (pintype "passive"))
      (node (ref "R67") (pin "1") (pinfunction "1_1") (pintype "passive"))
    )
    (net (code "23") (name "Net-(LED11-K)") (class "Default")
      (node (ref "LED11") (pin "2") (pinfunction "K_2") (pintype "passive"))
      (node (ref "R68") (pin "1") (pinfunction "1_1") (pintype "passive"))
    )
    (net (code "24") (name "Net-(LED12-K)") (class "Default")
      (node (ref "LED12") (pin "2") (pinfunction "K_2") (pintype "passive"))
      (node (ref "R76") (pin "1") (pinfunction "1_1") (pintype "passive"))
    )
    (net (code "25") (name "Net-(LED13-K)") (class "Default")
      (node (ref "LED13") (pin "2") (pinfunction "K_2") (pintype "passive"))
      (node (ref "R77") (pin "1") (pinfunction "1_1") (pintype "passive"))
    )
    (net (code "26") (name "Net-(U7-DEN)") (class "Default")
      (node (ref "R55") (pin "7") (pinfunction "7_7") (pintype "passive"))
      (node (ref "U7") (pin "3") (pinfunction "DEN_3") (pintype "passive"))
    )
    (net (code "27") (name "Net-(U7-DSEL)") (class "Default")
      (node (ref "R55") (pin "6") (pinfunction "6_6") (pintype "passive"))
      (node (ref "U7") (pin "5") (pinfunction "DSEL_5") (pintype "passive"))
    )
    (net (code "28") (name "Net-(U7-GND)") (class "Default")
      (node (ref "R62") (pin "1") (pinfunction "1_1") (pintype "passive"))
      (node (ref "U7") (pin "1") (pinfunction "GND_1") (pintype "passive"))
    )
    (net (code "29") (name "Net-(U7-IN0)") (class "Default")
      (node (ref "R55") (pin "8") (pinfunction "8_8") (pintype "passive"))
      (node (ref "U7") (pin "2") (pinfunction "IN0_2") (pintype "passive"))
    )
    (net (code "30") (name "Net-(U7-IN1)") (class "Default")
      (node (ref "R55") (pin "5") (pinfunction "5_5") (pintype "passive"))
      (node (ref "U7") (pin "6") (pinfunction "IN1_6") (pintype "passive"))
    )
    (net (code "31") (name "Net-(U7-IS)") (class "Default")
      (node (ref "R64") (pin "2") (pinfunction "2_2") (pintype "passive"))
      (node (ref "R66") (pin "1") (pinfunction "1_1") (pintype "passive"))
      (node (ref "U7") (pin "4") (pinfunction "IS_4") (pintype "passive"))
    )
    (net (code "32") (name "Net-(U8-DEN)") (class "Default")
      (node (ref "R54") (pin "2") (pinfunction "2_2") (pintype "passive"))
      (node (ref "U8") (pin "3") (pinfunction "DEN_3") (pintype "passive"))
    )
    (net (code "33") (name "Net-(U8-GND)") (class "Default")
      (node (ref "R60") (pin "1") (pinfunction "1_1") (pintype "passive"))
      (node (ref "U8") (pin "1") (pinfunction "GND_1") (pintype "passive"))
    )
    (net (code "34") (name "Net-(U8-IN)") (class "Default")
      (node (ref "R57") (pin "2") (pinfunction "2_2") (pintype "passive"))
      (node (ref "U8") (pin "2") (pinfunction "IN_2") (pintype "passive"))
    )
    (net (code "35") (name "Net-(U8-IS)") (class "Default")
      (node (ref "R58") (pin "2") (pinfunction "2_2") (pintype "passive"))
      (node (ref "R63") (pin "1") (pinfunction "1_1") (pintype "passive"))
      (node (ref "U8") (pin "4") (pinfunction "IS_4") (pintype "passive"))
    )
    (net (code "36") (name "Net-(U9-DEN)") (class "Default")
      (node (ref "R69") (pin "7") (pinfunction "7_7") (pintype "passive"))
      (node (ref "U9") (pin "3") (pinfunction "DEN_3") (pintype "passive"))
    )
    (net (code "37") (name "Net-(U9-DSEL)") (class "Default")
      (node (ref "R69") (pin "6") (pinfunction "6_6") (pintype "passive"))
      (node (ref "U9") (pin "5") (pinfunction "DSEL_5") (pintype "passive"))
    )
    (net (code "38") (name "Net-(U9-GND)") (class "Default")
      (node (ref "R72") (pin "1") (pinfunction "1_1") (pintype "passive"))
      (node (ref "U9") (pin "1") (pinfunction "GND_1") (pintype "passive"))
    )
    (net (code "39") (name "Net-(U9-IN0)") (class "Default")
      (node (ref "R69") (pin "8") (pinfunction "8_8") (pintype "passive"))
      (node (ref "U9") (pin "2") (pinfunction "IN0_2") (pintype "passive"))
    )
    (net (code "40") (name "Net-(U9-IN1)") (class "Default")
      (node (ref "R69") (pin "5") (pinfunction "5_5") (pintype "passive"))
      (node (ref "U9") (pin "6") (pinfunction "IN1_6") (pintype "passive"))
    )
    (net (code "41") (name "Net-(U9-IS)") (class "Default")
      (node (ref "R73") (pin "2") (pinfunction "2_2") (pintype "passive"))
      (node (ref "R75") (pin "1") (pinfunction "1_1") (pintype "passive"))
      (node (ref "U9") (pin "4") (pinfunction "IS_4") (pintype "passive"))
    )
    (net (code "42") (name "VBAT") (class "Default")
      (node (ref "C25") (pin "1") (pinfunction "1_1") (pintype "passive"))
      (node (ref "C26") (pin "1") (pinfunction "1_1") (pintype "passive"))
      (node (ref "C32") (pin "1") (pinfunction "1_1") (pintype "passive"))
      (node (ref "U7") (pin "15") (pinfunction "VS_15") (pintype "passive"))
      (node (ref "U8") (pin "15") (pinfunction "VS_15") (pintype "passive"))
      (node (ref "U9") (pin "15") (pinfunction "VS_15") (pintype "passive"))
    )
    (net (code "43") (name "unconnected-(Rear_Left_Brake_Light-21-Pad2)") (class "Default")
      (node (ref "Rear_Left_Brake_Light") (pin "2") (pinfunction "21_2") (pintype "passive"))
    )
    (net (code "44") (name "unconnected-(Rear_Left_Turn_Light-21-Pad2)") (class "Default")
      (node (ref "Rear_Left_Turn_Light") (pin "2") (pinfunction "21_2") (pintype "passive"))
    )
    (net (code "45") (name "unconnected-(Rear_Right_Brake_Light-21-Pad2)") (class "Default")
      (node (ref "Rear_Right_Brake_Light") (pin "2") (pinfunction "21_2") (pintype "passive"))
    )
    (net (code "46") (name "unconnected-(Rear_Right_Turn_Light-21-Pad2)") (class "Default")
      (node (ref "Rear_Right_Turn_Light") (pin "2") (pinfunction "21_2") (pintype "passive"))
    )
  )
)
